# ehomePower.net
KiCad netlist of a schematic drawn in EAGLE
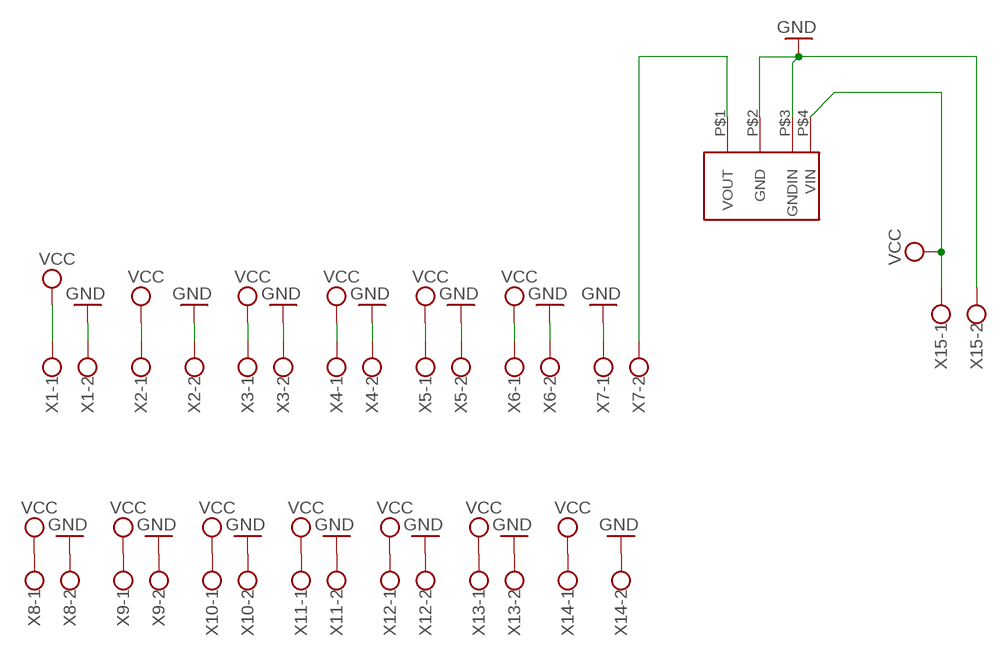
[diagram p0: schematic, sheet 1]

(export (version "E")
  (design (tool "Eeschema 10.0.6"))
  (components
    (comp (ref "U$2")
      (value "AM2DS")
      (footprint "eagle-import:AM2DS")
      (libsource (lib "eagle-import") (part "AM2DS"))
    )
    (comp (ref "X1")
      (value "W237-102")
      (footprint "eagle-import:W237-102")
      (fields (field (name "MPN") "237-102"))
      (libsource (lib "eagle-import") (part "W237-102"))
    )
    (comp (ref "X2")
      (value "W237-102")
      (footprint "eagle-import:W237-102")
      (fields (field (name "MPN") "237-102"))
      (libsource (lib "eagle-import") (part "W237-102"))
    )
    (comp (ref "X3")
      (value "W237-102")
      (footprint "eagle-import:W237-102")
      (fields (field (name "MPN") "237-102"))
      (libsource (lib "eagle-import") (part "W237-102"))
    )
    (comp (ref "X4")
      (value "W237-102")
      (footprint "eagle-import:W237-102")
      (fields (field (name "MPN") "237-102"))
      (libsource (lib "eagle-import") (part "W237-102"))
    )
    (comp (ref "X5")
      (value "W237-102")
      (footprint "eagle-import:W237-102")
      (fields (field (name "MPN") "237-102"))
      (libsource (lib "eagle-import") (part "W237-102"))
    )
    (comp (ref "X6")
      (value "W237-102")
      (footprint "eagle-import:W237-102")
      (fields (field (name "MPN") "237-102"))
      (libsource (lib "eagle-import") (part "W237-102"))
    )
    (comp (ref "X7")
      (value "W237-102")
      (footprint "eagle-import:W237-102")
      (fields (field (name "MPN") "237-102"))
      (libsource (lib "eagle-import") (part "W237-102"))
    )
    (comp (ref "X8")
      (value "W237-102")
      (footprint "eagle-import:W237-102")
      (fields (field (name "MPN") "237-102"))
      (libsource (lib "eagle-import") (part "W237-102"))
    )
    (comp (ref "X9")
      (value "W237-102")
      (footprint "eagle-import:W237-102")
      (fields (field (name "MPN") "237-102"))
      (libsource (lib "eagle-import") (part "W237-102"))
    )
    (comp (ref "X10")
      (value "W237-102")
      (footprint "eagle-import:W237-102")
      (fields (field (name "MPN") "237-102"))
      (libsource (lib "eagle-import") (part "W237-102"))
    )
    (comp (ref "X11")
      (value "W237-102")
      (footprint "eagle-import:W237-102")
      (fields (field (name "MPN") "237-102"))
      (libsource (lib "eagle-import") (part "W237-102"))
    )
    (comp (ref "X12")
      (value "W237-102")
      (footprint "eagle-import:W237-102")
      (fields (field (name "MPN") "237-102"))
      (libsource (lib "eagle-import") (part "W237-102"))
    )
    (comp (ref "X13")
      (value "W237-102")
      (footprint "eagle-import:W237-102")
      (fields (field (name "MPN") "237-102"))
      (libsource (lib "eagle-import") (part "W237-102"))
    )
    (comp (ref "X14")
      (value "W237-102")
      (footprint "eagle-import:W237-102")
      (fields (field (name "MPN") "237-102"))
      (libsource (lib "eagle-import") (part "W237-102"))
    )
    (comp (ref "X15")
      (value "W237-102")
      (footprint "eagle-import:W237-102")
      (fields (field (name "MPN") "237-102"))
      (libsource (lib "eagle-import") (part "W237-102"))
    )
  )
  (nets
    (net (code "1") (name "GND") (class "Default")
      (node (ref "U$2") (pin "P$2") (pinfunction "GND_P$2") (pintype "input"))
      (node (ref "U$2") (pin "P$3") (pinfunction "GNDIN_P$3") (pintype "input"))
      (node (ref "X1") (pin "2") (pinfunction "KL_2") (pintype "passive"))
      (node (ref "X10") (pin "2") (pinfunction "KL_2") (pintype "passive"))
      (node (ref "X11") (pin "2") (pinfunction "KL_2") (pintype "passive"))
      (node (ref "X12") (pin "2") (pinfunction "KL_2") (pintype "passive"))
      (node (ref "X13") (pin "2") (pinfunction "KL_2") (pintype "passive"))
      (node (ref "X14") (pin "2") (pinfunction "KL_2") (pintype "passive"))
      (node (ref "X15") (pin "2") (pinfunction "KL_2") (pintype "passive"))
      (node (ref "X2") (pin "2") (pinfunction "KL_2") (pintype "passive"))
      (node (ref "X3") (pin "2") (pinfunction "KL_2") (pintype "passive"))
      (node (ref "X4") (pin "2") (pinfunction "KL_2") (pintype "passive"))
      (node (ref "X5") (pin "2") (pinfunction "KL_2") (pintype "passive"))
      (node (ref "X6") (pin "2") (pinfunction "KL_2") (pintype "passive"))
      (node (ref "X7") (pin "1") (pinfunction "KL_1") (pintype "passive"))
      (node (ref "X8") (pin "2") (pinfunction "KL_2") (pintype "passive"))
      (node (ref "X9") (pin "2") (pinfunction "KL_2") (pintype "passive"))
    )
    (net (code "2") (name "Net-(U$2-VOUT)") (class "Default")
      (node (ref "U$2") (pin "P$1") (pinfunction "VOUT_P$1") (pintype "input"))
      (node (ref "X7") (pin "2") (pinfunction "KL_2") (pintype "passive"))
    )
    (net (code "3") (name "VCC") (class "Default")
      (node (ref "U$2") (pin "P$4") (pinfunction "VIN_P$4") (pintype "input"))
      (node (ref "X1") (pin "1") (pinfunction "KL_1") (pintype "passive"))
      (node (ref "X10") (pin "1") (pinfunction "KL_1") (pintype "passive"))
      (node (ref "X11") (pin "1") (pinfunction "KL_1") (pintype "passive"))
      (node (ref "X12") (pin "1") (pinfunction "KL_1") (pintype "passive"))
      (node (ref "X13") (pin "1") (pinfunction "KL_1") (pintype "passive"))
      (node (ref "X14") (pin "1") (pinfunction "KL_1") (pintype "passive"))
      (node (ref "X15") (pin "1") (pinfunction "KL_1") (pintype "passive"))
      (node (ref "X2") (pin "1") (pinfunction "KL_1") (pintype "passive"))
      (node (ref "X3") (pin "1") (pinfunction "KL_1") (pintype "passive"))
      (node (ref "X4") (pin "1") (pinfunction "KL_1") (pintype "passive"))
      (node (ref "X5") (pin "1") (pinfunction "KL_1") (pintype "passive"))
      (node (ref "X6") (pin "1") (pinfunction "KL_1") (pintype "passive"))
      (node (ref "X8") (pin "1") (pinfunction "KL_1") (pintype "passive"))
      (node (ref "X9") (pin "1") (pinfunction "KL_1") (pintype "passive"))
    )
  )
)
